# Power.net
KiCad netlist of a schematic drawn in Altium Designer
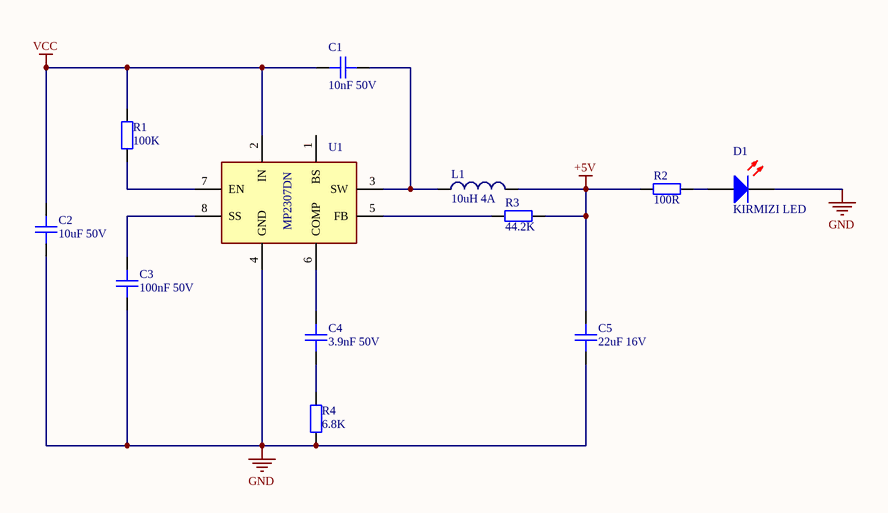
[diagram p0: Power.SchDoc]

(export (version "E")
  (design (tool "Eeschema 10.0.6"))
  (components
    (comp (ref "C1")
      (value "CAP CER 10000PF 50V X7R 0805")
      (footprint "CAP 0805/2012")
      (description "10000pF ±10% 50V Ceramic Capacitor X7R 0805 (2012 Metric)")
      (fields (field (name "DEGER") "10nF 50V"))
      (libsource (lib "PROJE") (part "10nF 50V 0805"))
    )
    (comp (ref "C2")
      (value "CAP CER 10UF 50V X5R 1206")
      (footprint "CAP 1206/3216")
      (description "10µF ±10% 50V Ceramic Capacitor X5R 1206 (3216 Metric)")
      (fields (field (name "DEGER") "10uF 50V"))
      (libsource (lib "PROJE") (part "10uF 50V 1206"))
    )
    (comp (ref "C3")
      (value "CAP CER 0.1UF 50V X7R 0805")
      (footprint "CAP 0805/2012")
      (description "0.1µF ±10% 50V Ceramic Capacitor X7R 0805 (2012 Metric)")
      (fields (field (name "DEGER") "100nF 50V"))
      (libsource (lib "PROJE") (part "100nF 50V 0805"))
    )
    (comp (ref "C4")
      (value "CAP CER 3900PF 50V X7R 0805")
      (footprint "CAP 0805/2012")
      (description "3900pF ±10% 50V Ceramic Capacitor X7R 0805 (2012 Metric)")
      (fields (field (name "DEGER") "3.9nF 50V"))
      (libsource (lib "PROJE") (part "3.9nF 50V 0805"))
    )
    (comp (ref "C5")
      (value "CAP CERAMIC 22UF 16V X7S 20% PAD")
      (footprint "CAP 1206/3216")
      (description "22µF ±20% 16V Ceramic Capacitor X7S 1206 (3216 Metric)")
      (fields (field (name "DEGER") "22uF 16V"))
      (libsource (lib "PROJE") (part "22uF 16V 1206"))
    )
    (comp (ref "D1")
      (value "Red 645nm LED Indication - Discrete 1.8V 0805")
      (footprint "SMD: LED 0805/2012 RED")
      (description "LED RED DIFFUSED 0805 SMD")
      (fields (field (name "DEGER") "KIRMIZI LED"))
      (libsource (lib "PROJE") (part "LED_Kırmızı"))
    )
    (comp (ref "L1")
      (value "FIXED IND 10UH 4A 68 MOHM SMD")
      (footprint "ASPI-0630LR-100M-T15")
      (description "10µH Shielded Molded Inductor 4A 68mOhm Max Nonstandard")
      (fields (field (name "DEGER") "10uH 4A"))
      (libsource (lib "PROJE") (part "10uH 4A"))
    )
    (comp (ref "R1")
      (value "RES SMD 100K OHM 1% 1/8W 0805")
      (footprint "RES_0805")
      (description "100 kOhms ±1% 0.125W, 1/8W Chip Resistor 0805 (2012 Metric) Moisture Resistant Thick Film")
      (fields (field (name "DEGER") "100K"))
      (libsource (lib "PROJE") (part "100K 0805"))
    )
    (comp (ref "R2")
      (value "RES SMD 100 OHM 1% 1/8W 0805")
      (footprint "RES_0805")
      (description "100 Ohms ±1% 0.125W, 1/8W Chip Resistor 0805 (2012 Metric) Moisture Resistant Thick Film")
      (fields (field (name "DEGER") "100R"))
      (libsource (lib "PROJE") (part "100R 0805"))
    )
    (comp (ref "R3")
      (value "RES SMD 44.2K OHM 1% 1/8W 0805")
      (footprint "RES_0805")
      (description "44.2 kOhms ±1% 0.125W, 1/8W Chip Resistor 0805 (2012 Metric) Moisture Resistant Thick Film")
      (fields (field (name "DEGER") "44.2K"))
      (libsource (lib "PROJE") (part "44.2K 0805"))
    )
    (comp (ref "R4")
      (value "RES SMD 6.8K OHM 1% 1/8W 0805")
      (footprint "RES_0805")
      (description "6.8 kOhms ±1% 0.125W, 1/8W Chip Resistor 0805 (2012 Metric) Moisture Resistant Thick Film")
      (fields (field (name "DEGER") "6.8K"))
      (libsource (lib "PROJE") (part "6.8K 0805"))
    )
    (comp (ref "U1")
      (value "IC REG BUCK ADJUSTABLE 3A 8SOIC")
      (footprint "SOIC8_PAD")
      (fields (field (name "DEGER") "MP2307DN"))
      (libsource (lib "PROJE") (part "MP2307DN"))
    )
  )
  (nets
    (net (code "1") (name "+5V") (class "Default")
      (node (ref "C5") (pin "2") (pinfunction "2_2") (pintype "passive"))
      (node (ref "L1") (pin "2") (pinfunction "2_2") (pintype "passive"))
      (node (ref "R2") (pin "1") (pinfunction "1_1") (pintype "passive"))
      (node (ref "R3") (pin "2") (pinfunction "2_2") (pintype "passive"))
    )
    (net (code "2") (name "GND") (class "Default")
      (node (ref "C2") (pin "1") (pinfunction "1_1") (pintype "passive"))
      (node (ref "C3") (pin "1") (pinfunction "1_1") (pintype "passive"))
      (node (ref "C5") (pin "1") (pinfunction "1_1") (pintype "passive"))
      (node (ref "D1") (pin "2") (pinfunction "K_2") (pintype "passive"))
      (node (ref "R4") (pin "1") (pinfunction "1_1") (pintype "passive"))
      (node (ref "U1") (pin "4") (pinfunction "GND_4") (pintype "passive"))
    )
    (net (code "3") (name "Net-(C4-Pad1)") (class "Default")
      (node (ref "C4") (pin "1") (pinfunction "1_1") (pintype "passive"))
      (node (ref "R4") (pin "2") (pinfunction "2_2") (pintype "passive"))
    )
    (net (code "4") (name "Net-(D1-A)") (class "Default")
      (node (ref "D1") (pin "1") (pinfunction "A_1") (pintype "passive"))
      (node (ref "R2") (pin "2") (pinfunction "2_2") (pintype "passive"))
    )
    (net (code "5") (name "Net-(U1-COMP)") (class "Default")
      (node (ref "C4") (pin "2") (pinfunction "2_2") (pintype "passive"))
      (node (ref "U1") (pin "6") (pinfunction "COMP_6") (pintype "passive"))
    )
    (net (code "6") (name "Net-(U1-EN)") (class "Default")
      (node (ref "R1") (pin "1") (pinfunction "1_1") (pintype "passive"))
      (node (ref "U1") (pin "7") (pinfunction "EN_7") (pintype "passive"))
    )
    (net (code "7") (name "Net-(U1-FB)") (class "Default")
      (node (ref "R3") (pin "1") (pinfunction "1_1") (pintype "passive"))
      (node (ref "U1") (pin "5") (pinfunction "FB_5") (pintype "passive"))
    )
    (net (code "8") (name "Net-(U1-SS)") (class "Default")
      (node (ref "C3") (pin "2") (pinfunction "2_2") (pintype "passive"))
      (node (ref "U1") (pin "8") (pinfunction "SS_8") (pintype "passive"))
    )
    (net (code "9") (name "Net-(U1-SW)") (class "Default")
      (node (ref "C1") (pin "2") (pinfunction "2_2") (pintype "passive"))
      (node (ref "L1") (pin "1") (pinfunction "1_1") (pintype "passive"))
      (node (ref "U1") (pin "3") (pinfunction "SW_3") (pintype "passive"))
    )
    (net (code "10") (name "VCC") (class "Default")
      (node (ref "C1") (pin "1") (pinfunction "1_1") (pintype "passive"))
      (node (ref "C2") (pin "2") (pinfunction "2_2") (pintype "passive"))
      (node (ref "R1") (pin "2") (pinfunction "2_2") (pintype "passive"))
      (node (ref "U1") (pin "2") (pinfunction "IN_2") (pintype "passive"))
    )
    (net (code "11") (name "unconnected-(U1-BS-Pad1)") (class "Default")
      (node (ref "U1") (pin "1") (pinfunction "BS_1") (pintype "passive"))
    )
  )
)
